# DPAD.net
KiCad netlist of a schematic drawn in Altium Designer
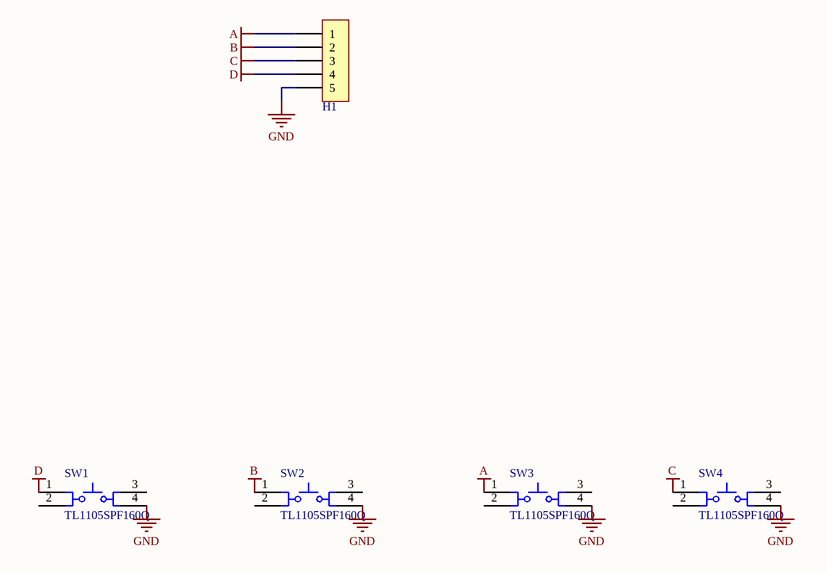
[diagram p0: DPAD.SchDoc]

(export (version "E")
  (design (tool "Eeschema 10.0.6"))
  (components
    (comp (ref "H1")
      (value "HDR,2.54mm,1x5")
      (footprint "APSS Connectors:HEADER_2.54MM_1x5PIN")
      (description "Connector - 2.54mm, 1x5-pin")
      (libsource (lib "APSS Connectors") (part "HDR,2.54mm,1x5"))
    )
    (comp (ref "SW1")
      (value "TL1105SPF160Q")
      (footprint "ESWI-TL1105SPF_V")
      (description "Tact Switch, SPST-NO, 50 mA, 12 VDC, -20 to 70 degC, 4-Pin THD, RoHS, Bulk")
      (fields (field (name "MANUFACTURER") "E-Switch"))
      (libsource (lib "New tactile switch") (part "CMP-2000-07248-1"))
    )
    (comp (ref "SW2")
      (value "TL1105SPF160Q")
      (footprint "ESWI-TL1105SPF_V")
      (description "Tact Switch, SPST-NO, 50 mA, 12 VDC, -20 to 70 degC, 4-Pin THD, RoHS, Bulk")
      (fields (field (name "MANUFACTURER") "E-Switch"))
      (libsource (lib "New tactile switch") (part "CMP-2000-07248-1"))
    )
    (comp (ref "SW3")
      (value "TL1105SPF160Q")
      (footprint "ESWI-TL1105SPF_V")
      (description "Tact Switch, SPST-NO, 50 mA, 12 VDC, -20 to 70 degC, 4-Pin THD, RoHS, Bulk")
      (fields (field (name "MANUFACTURER") "E-Switch"))
      (libsource (lib "New tactile switch") (part "CMP-2000-07248-1"))
    )
    (comp (ref "SW4")
      (value "TL1105SPF160Q")
      (footprint "ESWI-TL1105SPF_V")
      (description "Tact Switch, SPST-NO, 50 mA, 12 VDC, -20 to 70 degC, 4-Pin THD, RoHS, Bulk")
      (fields (field (name "MANUFACTURER") "E-Switch"))
      (libsource (lib "New tactile switch") (part "CMP-2000-07248-1"))
    )
  )
  (nets
    (net (code "1") (name "A") (class "Default")
      (node (ref "H1") (pin "1") (pinfunction "1_1") (pintype "passive"))
      (node (ref "SW3") (pin "1") (pinfunction "1_1") (pintype "passive"))
    )
    (net (code "2") (name "B") (class "Default")
      (node (ref "H1") (pin "2") (pinfunction "2_2") (pintype "passive"))
      (node (ref "SW2") (pin "1") (pinfunction "1_1") (pintype "passive"))
    )
    (net (code "3") (name "C") (class "Default")
      (node (ref "H1") (pin "3") (pinfunction "3_3") (pintype "passive"))
      (node (ref "SW4") (pin "1") (pinfunction "1_1") (pintype "passive"))
    )
    (net (code "4") (name "D") (class "Default")
      (node (ref "H1") (pin "4") (pinfunction "4_4") (pintype "passive"))
      (node (ref "SW1") (pin "1") (pinfunction "1_1") (pintype "passive"))
    )
    (net (code "5") (name "GND") (class "Default")
      (node (ref "H1") (pin "5") (pinfunction "5_5") (pintype "passive"))
      (node (ref "SW1") (pin "4") (pinfunction "4_4") (pintype "passive"))
      (node (ref "SW2") (pin "4") (pinfunction "4_4") (pintype "passive"))
      (node (ref "SW3") (pin "4") (pinfunction "4_4") (pintype "passive"))
      (node (ref "SW4") (pin "4") (pinfunction "4_4") (pintype "passive"))
    )
    (net (code "6") (name "unconnected-(SW1-Pad2)") (class "Default")
      (node (ref "SW1") (pin "2") (pinfunction "2_2") (pintype "passive"))
    )
    (net (code "7") (name "unconnected-(SW1-Pad3)") (class "Default")
      (node (ref "SW1") (pin "3") (pinfunction "3_3") (pintype "passive"))
    )
    (net (code "8") (name "unconnected-(SW2-Pad2)") (class "Default")
      (node (ref "SW2") (pin "2") (pinfunction "2_2") (pintype "passive"))
    )
    (net (code "9") (name "unconnected-(SW2-Pad3)") (class "Default")
      (node (ref "SW2") (pin "3") (pinfunction "3_3") (pintype "passive"))
    )
    (net (code "10") (name "unconnected-(SW3-Pad2)") (class "Default")
      (node (ref "SW3") (pin "2") (pinfunction "2_2") (pintype "passive"))
    )
    (net (code "11") (name "unconnected-(SW3-Pad3)") (class "Default")
      (node (ref "SW3") (pin "3") (pinfunction "3_3") (pintype "passive"))
    )
    (net (code "12") (name "unconnected-(SW4-Pad2)") (class "Default")
      (node (ref "SW4") (pin "2") (pinfunction "2_2") (pintype "passive"))
    )
    (net (code "13") (name "unconnected-(SW4-Pad3)") (class "Default")
      (node (ref "SW4") (pin "3") (pinfunction "3_3") (pintype "passive"))
    )
  )
)
